# SGP30_breakout.net
KiCad netlist of a schematic drawn in EAGLE
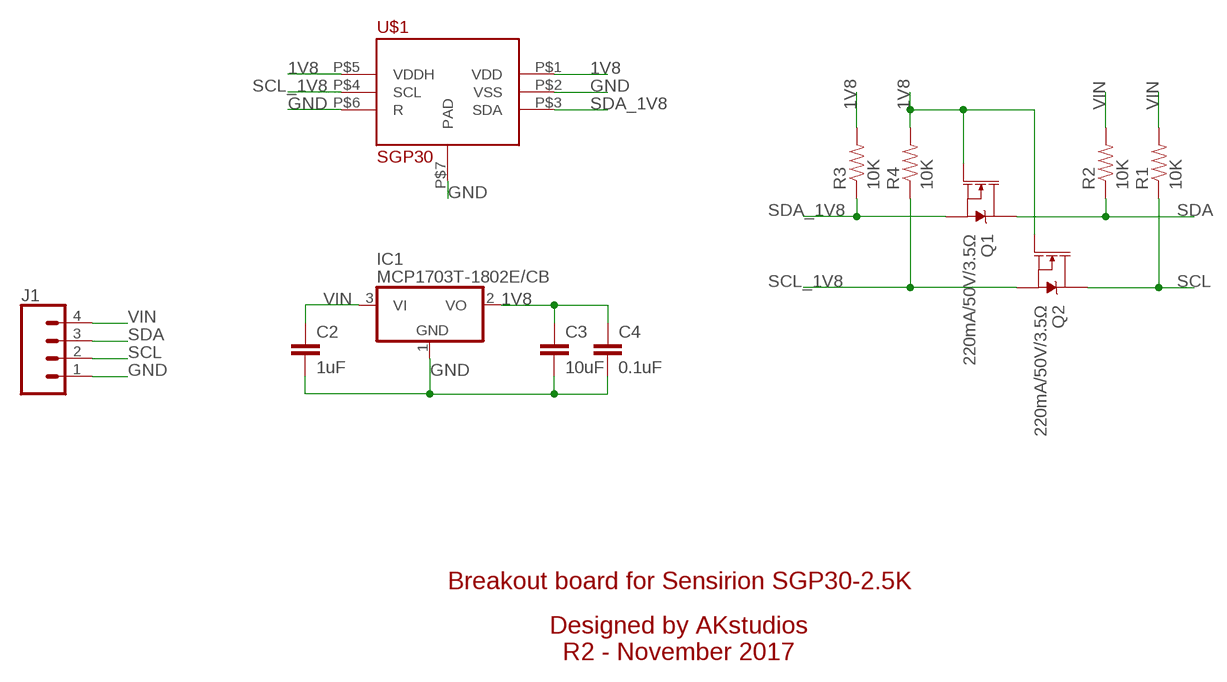
[diagram p0: schematic, sheet 1]

(export (version "E")
  (design (tool "Eeschema 10.0.6"))
  (components
    (comp (ref "C2")
      (value "1uF")
      (footprint "eagle-import:0805")
      (libsource (lib "eagle-import") (part "CAP0805"))
    )
    (comp (ref "C3")
      (value "10uF")
      (footprint "eagle-import:0805")
      (libsource (lib "eagle-import") (part "CAP0805"))
    )
    (comp (ref "C4")
      (value "0.1uF")
      (footprint "eagle-import:0805")
      (libsource (lib "eagle-import") (part "CAP0805"))
    )
    (comp (ref "IC1")
      (value "MCP1703T-1802E/CB")
      (footprint "eagle-import:SOT23")
      (libsource (lib "eagle-import") (part "MCP1703CB"))
    )
    (comp (ref "J1")
      (value "CONN_04")
      (footprint "eagle-import:1X04")
      (libsource (lib "eagle-import") (part "CONN_04"))
    )
    (comp (ref "Q1")
      (value "220mA/50V/3.5Ω")
      (footprint "eagle-import:SOT23-3")
      (libsource (lib "eagle-import") (part "MOSFET-NCH-BSS138"))
    )
    (comp (ref "Q2")
      (value "220mA/50V/3.5Ω")
      (footprint "eagle-import:SOT23-3")
      (libsource (lib "eagle-import") (part "MOSFET-NCH-BSS138"))
    )
    (comp (ref "R1")
      (value "10K")
      (footprint "eagle-import:0805")
      (libsource (lib "eagle-import") (part "RESISTOR0805-RES"))
    )
    (comp (ref "R2")
      (value "10K")
      (footprint "eagle-import:0805")
      (libsource (lib "eagle-import") (part "RESISTOR0805-RES"))
    )
    (comp (ref "R3")
      (value "10K")
      (footprint "eagle-import:0805")
      (libsource (lib "eagle-import") (part "RESISTOR0805-RES"))
    )
    (comp (ref "R4")
      (value "10K")
      (footprint "eagle-import:0805")
      (libsource (lib "eagle-import") (part "RESISTOR0805-RES"))
    )
    (comp (ref "U$1")
      (value "SGP30")
      (footprint "eagle-import:DFN")
      (libsource (lib "eagle-import") (part "SGP30"))
    )
  )
  (nets
    (net (code "1") (name "/1V8") (class "Default")
      (node (ref "C3") (pin "1") (pinfunction "1_1") (pintype "passive"))
      (node (ref "C4") (pin "1") (pinfunction "1_1") (pintype "passive"))
      (node (ref "IC1") (pin "2") (pinfunction "VO_2") (pintype "passive"))
      (node (ref "Q1") (pin "1") (pinfunction "G_1") (pintype "bidirectional"))
      (node (ref "Q2") (pin "1") (pinfunction "G_1") (pintype "bidirectional"))
      (node (ref "R3") (pin "2") (pinfunction "2_2") (pintype "passive"))
      (node (ref "R4") (pin "2") (pinfunction "2_2") (pintype "passive"))
      (node (ref "U$1") (pin "P$1") (pinfunction "VDD_P$1") (pintype "bidirectional"))
      (node (ref "U$1") (pin "P$5") (pinfunction "VDDH_P$5") (pintype "bidirectional"))
    )
    (net (code "2") (name "/GND") (class "Default")
      (node (ref "C2") (pin "2") (pinfunction "2_2") (pintype "passive"))
      (node (ref "C3") (pin "2") (pinfunction "2_2") (pintype "passive"))
      (node (ref "C4") (pin "2") (pinfunction "2_2") (pintype "passive"))
      (node (ref "IC1") (pin "1") (pinfunction "GND_1") (pintype "passive"))
      (node (ref "J1") (pin "1") (pinfunction "1_1") (pintype "passive"))
      (node (ref "U$1") (pin "P$2") (pinfunction "VSS_P$2") (pintype "bidirectional"))
      (node (ref "U$1") (pin "P$6") (pinfunction "R_P$6") (pintype "bidirectional"))
      (node (ref "U$1") (pin "P$7") (pinfunction "PAD_P$7") (pintype "bidirectional"))
    )
    (net (code "3") (name "/SCL") (class "Default")
      (node (ref "J1") (pin "2") (pinfunction "2_2") (pintype "passive"))
      (node (ref "Q2") (pin "3") (pinfunction "D_3") (pintype "bidirectional"))
      (node (ref "R1") (pin "1") (pinfunction "1_1") (pintype "passive"))
    )
    (net (code "4") (name "/SCL_1V8") (class "Default")
      (node (ref "Q2") (pin "2") (pinfunction "S_2") (pintype "bidirectional"))
      (node (ref "R4") (pin "1") (pinfunction "1_1") (pintype "passive"))
      (node (ref "U$1") (pin "P$4") (pinfunction "SCL_P$4") (pintype "bidirectional"))
    )
    (net (code "5") (name "/SDA") (class "Default")
      (node (ref "J1") (pin "3") (pinfunction "3_3") (pintype "passive"))
      (node (ref "Q1") (pin "3") (pinfunction "D_3") (pintype "bidirectional"))
      (node (ref "R2") (pin "1") (pinfunction "1_1") (pintype "passive"))
    )
    (net (code "6") (name "/SDA_1V8") (class "Default")
      (node (ref "Q1") (pin "2") (pinfunction "S_2") (pintype "bidirectional"))
      (node (ref "R3") (pin "1") (pinfunction "1_1") (pintype "passive"))
      (node (ref "U$1") (pin "P$3") (pinfunction "SDA_P$3") (pintype "bidirectional"))
    )
    (net (code "7") (name "/VIN") (class "Default")
      (node (ref "C2") (pin "1") (pinfunction "1_1") (pintype "passive"))
      (node (ref "IC1") (pin "3") (pinfunction "VI_3") (pintype "input"))
      (node (ref "J1") (pin "4") (pinfunction "4_4") (pintype "passive"))
      (node (ref "R1") (pin "2") (pinfunction "2_2") (pintype "passive"))
      (node (ref "R2") (pin "2") (pinfunction "2_2") (pintype "passive"))
    )
  )
)
